# MCU.net
KiCad netlist of a schematic drawn in Altium Designer
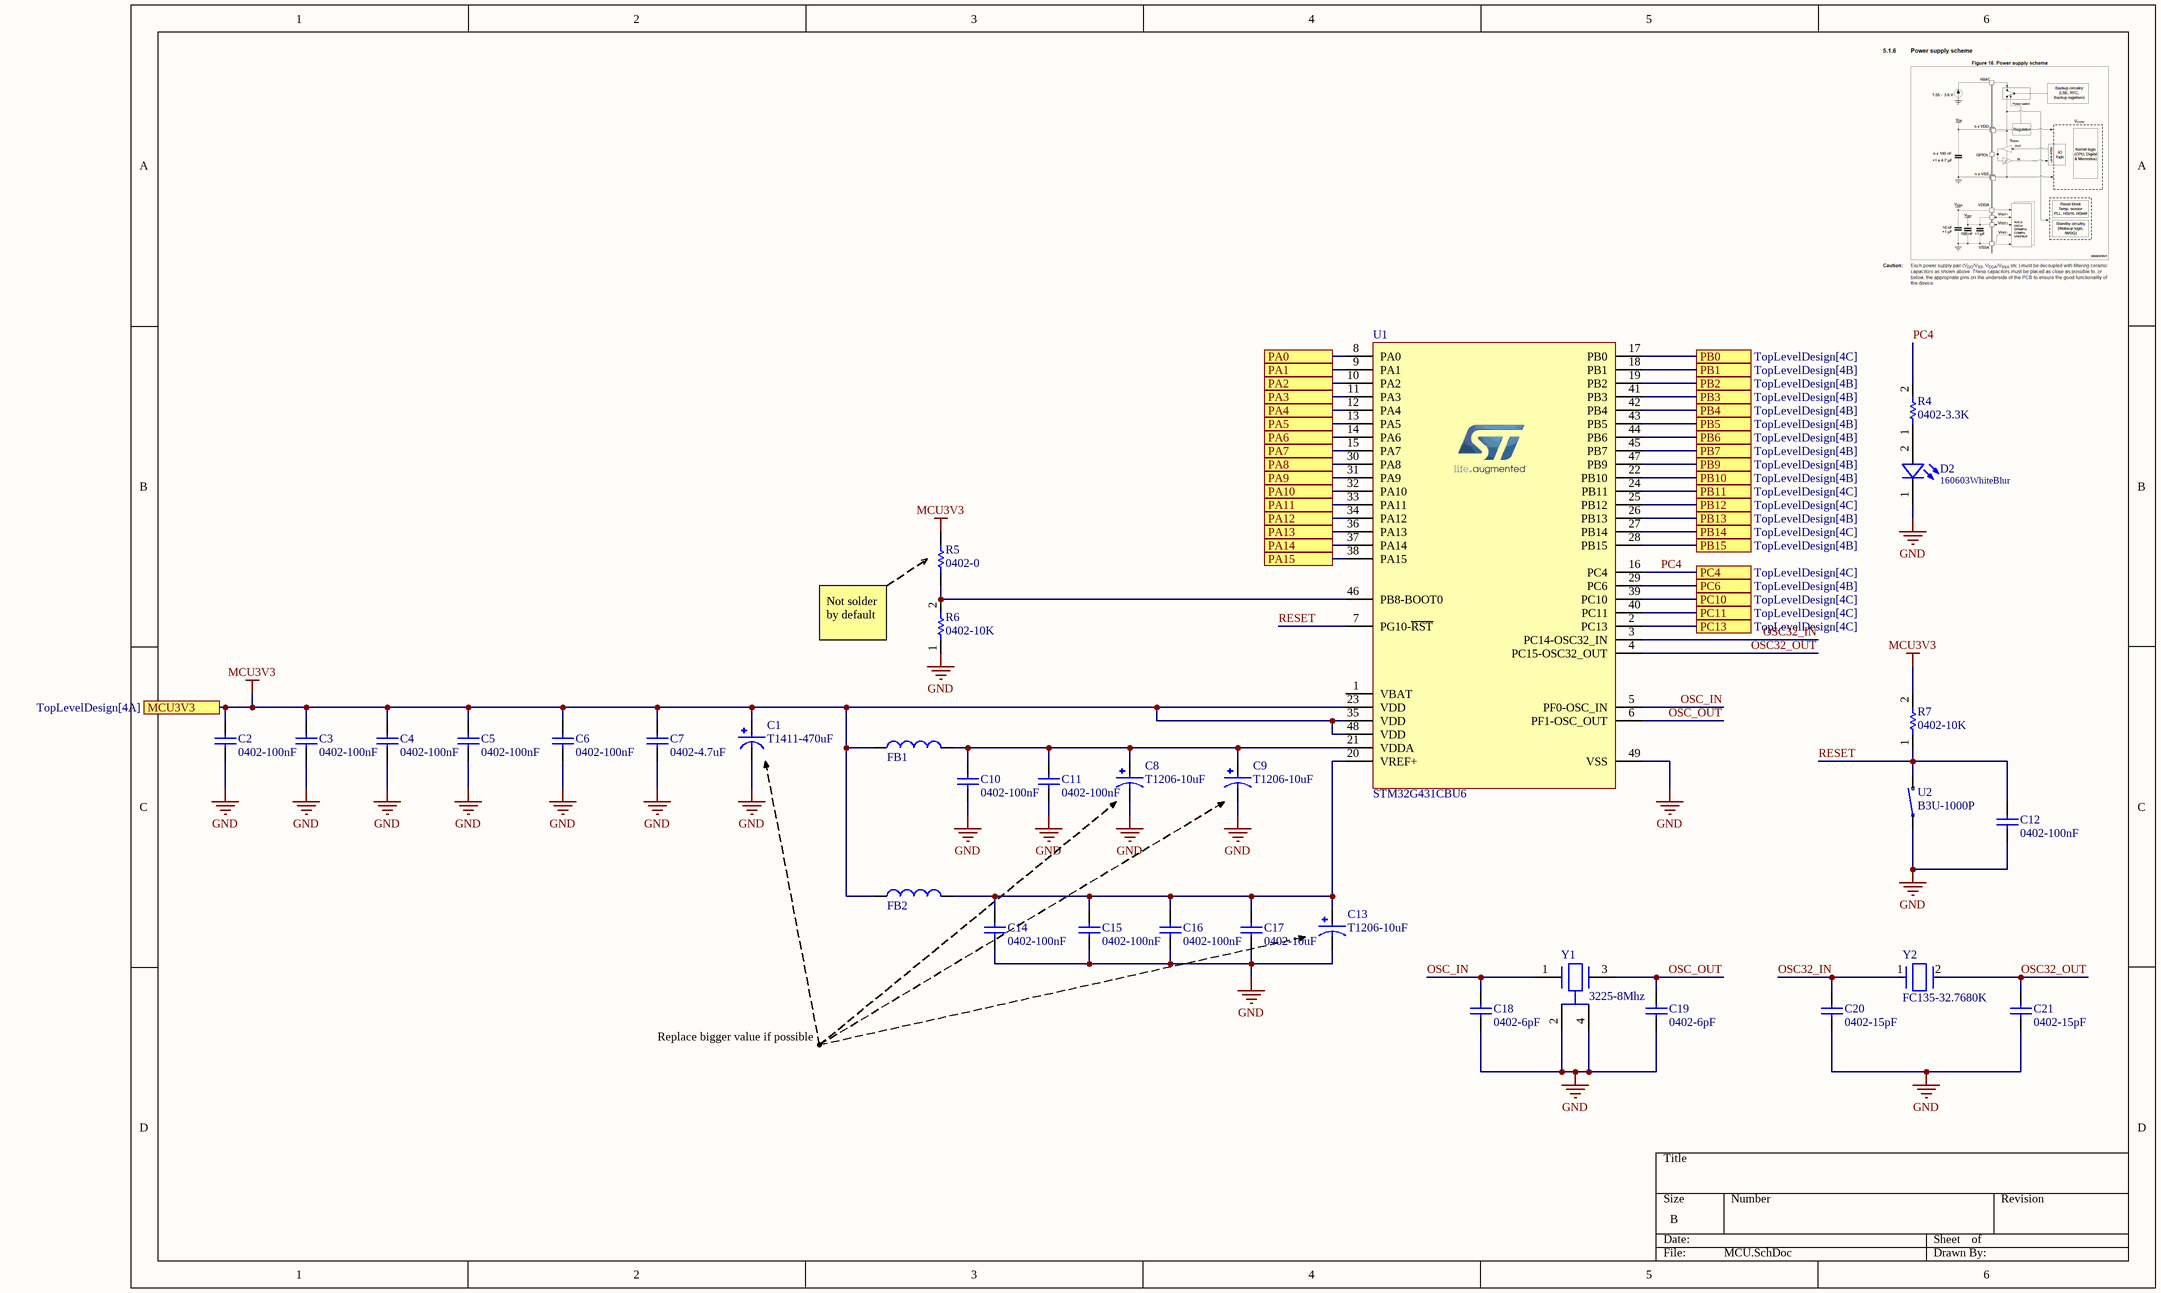
[diagram p0: MCU.SchDoc]

(export (version "E")
  (design (tool "Eeschema 10.0.6"))
  (components
    (comp (ref "C1")
      (value "T1411-470uF")
      (footprint "CAPPC3528X210N")
      (description "470 µF Molded Tantalum Polymer Capacitor 25 V 1411 (3528 Metric), 1210 150mOhm @ 100kHz")
      (fields (field (name "MP") "TCJB106M025R0150") (field (name "MF") "AVX"))
      (libsource (lib "Tin Tran") (part "T1411-10uF"))
    )
    (comp (ref "C2")
      (value "0402-100nF")
      (footprint "CAPC0402(1005)60_N")
      (description "Capacitor 100nF 0402")
      (fields (field (name "TOLERANCE") "20%"))
      (libsource (lib "Tin Tran") (part "0402"))
    )
    (comp (ref "C3")
      (value "0402-100nF")
      (footprint "CAPC0402(1005)60_N")
      (description "Capacitor 100nF 0402")
      (fields (field (name "TOLERANCE") "20%"))
      (libsource (lib "Tin Tran") (part "0402"))
    )
    (comp (ref "C4")
      (value "0402-100nF")
      (footprint "CAPC0402(1005)60_N")
      (description "Capacitor 100nF 0402")
      (fields (field (name "TOLERANCE") "20%"))
      (libsource (lib "Tin Tran") (part "0402"))
    )
    (comp (ref "C5")
      (value "0402-100nF")
      (footprint "CAPC0402(1005)60_N")
      (description "Capacitor 100nF 0402")
      (fields (field (name "TOLERANCE") "20%"))
      (libsource (lib "Tin Tran") (part "0402"))
    )
    (comp (ref "C6")
      (value "0402-100nF")
      (footprint "CAPC0402(1005)60_N")
      (description "Capacitor 100nF 0402")
      (fields (field (name "TOLERANCE") "20%"))
      (libsource (lib "Tin Tran") (part "0402"))
    )
    (comp (ref "C7")
      (value "0402-4.7uF")
      (footprint "CAPC0402(1005)60_N")
      (description "Capacitor 4.7uF 0402")
      (fields (field (name "TOLERANCE") "20%"))
      (libsource (lib "Tin Tran") (part "0402"))
    )
    (comp (ref "C8")
      (value "T1206-10uF")
      (footprint "CAPMP3216X180N")
      (description "Tantalum Capacitors - Polymer SMD 6.3V 47uF 1206 10% ESR=150mOhms")
      (fields (field (name "MP") "T543A476K006ATW150") (field (name "MF") "KEMET"))
      (libsource (lib "Tin Tran") (part "T1206-10uF"))
    )
    (comp (ref "C9")
      (value "T1206-10uF")
      (footprint "CAPMP3216X180N")
      (description "Tantalum Capacitors - Polymer SMD 6.3V 47uF 1206 10% ESR=150mOhms")
      (fields (field (name "MP") "T543A476K006ATW150") (field (name "MF") "KEMET"))
      (libsource (lib "Tin Tran") (part "T1206-10uF"))
    )
    (comp (ref "C10")
      (value "0402-100nF")
      (footprint "CAPC0402(1005)60_N")
      (description "Capacitor 100nF 0402")
      (fields (field (name "TOLERANCE") "20%"))
      (libsource (lib "Tin Tran") (part "0402"))
    )
    (comp (ref "C11")
      (value "0402-100nF")
      (footprint "CAPC0402(1005)60_N")
      (description "Capacitor 100nF 0402")
      (fields (field (name "TOLERANCE") "20%"))
      (libsource (lib "Tin Tran") (part "0402"))
    )
    (comp (ref "C12")
      (value "0402-100nF")
      (footprint "CAPC0402(1005)60_N")
      (description "Capacitor 100nF 0402")
      (fields (field (name "TOLERANCE") "20%"))
      (libsource (lib "Tin Tran") (part "0402"))
    )
    (comp (ref "C13")
      (value "T1206-10uF")
      (footprint "CAPMP3216X180N")
      (description "Tantalum Capacitors - Polymer SMD 6.3V 47uF 1206 10% ESR=150mOhms")
      (fields (field (name "MP") "T543A476K006ATW150") (field (name "MF") "KEMET"))
      (libsource (lib "Tin Tran") (part "T1206-10uF"))
    )
    (comp (ref "C14")
      (value "0402-100nF")
      (footprint "CAPC0402(1005)60_N")
      (description "Capacitor 100nF 0402")
      (fields (field (name "TOLERANCE") "20%"))
      (libsource (lib "Tin Tran") (part "0402"))
    )
    (comp (ref "C15")
      (value "0402-100nF")
      (footprint "CAPC0402(1005)60_N")
      (description "Capacitor 100nF 0402")
      (fields (field (name "TOLERANCE") "20%"))
      (libsource (lib "Tin Tran") (part "0402"))
    )
    (comp (ref "C16")
      (value "0402-100nF")
      (footprint "CAPC0402(1005)60_N")
      (description "Capacitor 100nF 0402")
      (fields (field (name "TOLERANCE") "20%"))
      (libsource (lib "Tin Tran") (part "0402"))
    )
    (comp (ref "C17")
      (value "0402-10uF")
      (footprint "CAPC0402(1005)60_N")
      (description "Capacitor 10uF 0402s")
      (fields (field (name "TOLERANCE") "20%"))
      (libsource (lib "Tin Tran") (part "0402"))
    )
    (comp (ref "C18")
      (value "0402-6pF")
      (footprint "CAPC0402(1005)60_N")
      (description "Capacitor 6pF 0402")
      (fields (field (name "TOLERANCE") "20%"))
      (libsource (lib "Tin Tran") (part "0402"))
    )
    (comp (ref "C19")
      (value "0402-6pF")
      (footprint "CAPC0402(1005)60_N")
      (description "Capacitor 6pF 0402")
      (fields (field (name "TOLERANCE") "20%"))
      (libsource (lib "Tin Tran") (part "0402"))
    )
    (comp (ref "C20")
      (value "0402-15pF")
      (footprint "CAPC0402(1005)60_N")
      (description "Capacitor 15pF 0402")
      (fields (field (name "TOLERANCE") "20%"))
      (libsource (lib "Tin Tran") (part "Copy of 0402"))
    )
    (comp (ref "C21")
      (value "0402-15pF")
      (footprint "CAPC0402(1005)60_N")
      (description "Capacitor 15pF 0402")
      (fields (field (name "TOLERANCE") "20%"))
      (libsource (lib "Tin Tran") (part "Copy of 0402"))
    )
    (comp (ref "D2")
      (value "160603WhiteBlur")
      (footprint "WL-SMCW_0603_H=0.7mm")
      (description "WL-SMCW SMT Mono-color Chip LED Blur, size 0603, White")
      (libsource (lib "Tin Tran") (part "160603WhiteClear"))
    )
    (comp (ref "FB1")
      (value "03060360110225")
      (footprint "FER_0603")
      (description "Ferrite, 0603, 600 Ohms, 300 mA")
      (fields (field (name "TOLERANCE") "25%"))
      (libsource (lib "Tin Tran") (part "03060380020125"))
    )
    (comp (ref "FB2")
      (value "03060360110225")
      (footprint "FER_0603")
      (description "Ferrite, 0603, 600 Ohms, 300 mA")
      (fields (field (name "TOLERANCE") "25%"))
      (libsource (lib "Tin Tran") (part "03060380020125"))
    )
    (comp (ref "R4")
      (value "0402-3.3K")
      (footprint "R-0402-10K")
      (description "RES 0402 3.3K")
      (libsource (lib "") (part "0402_1"))
    )
    (comp (ref "R5")
      (value "0402-0")
      (footprint "R-0402-1K")
      (description "0402Resistor 0 Ohm")
      (libsource (lib "") (part "0402_2"))
    )
    (comp (ref "R6")
      (value "0402-10K")
      (footprint "R-0402-10K")
      (description "RES 0402 10K")
      (libsource (lib "") (part "0402_1"))
    )
    (comp (ref "R7")
      (value "0402-10K")
      (footprint "R-0402-10K")
      (description "RES 0402 10K")
      (libsource (lib "") (part "0402_1"))
    )
    (comp (ref "U1")
      (value "STM32G431CBU6")
      (footprint "QFN50P700X700X60-49N")
      (fields (field (name "MF") "STMicroelectronics"))
      (libsource (lib "Tin Tran") (part "STM32G431CBU6"))
    )
    (comp (ref "U2")
      (value "B3U-1000P")
      (footprint "SODFL4025X160N")
      (description "Switch Tactile N.O. SPST Round Button Gull Wing 0.05A 12VDC 1.5N SMD T/R")
      (fields (field (name "MP") "B3U1000P") (field (name "MF") "Omron"))
      (libsource (lib "Tin Tran") (part "B3U-1000P"))
    )
    (comp (ref "Y1")
      (value "3225-8Mhz")
      (footprint "FP-NX3225SA-MFG")
      (description "CRYSTAL 8MHZ 8PF SMD")
      (fields (field (name "TOLERANCE") "15ppm") (field (name "MANUFACTURER") "NDK"))
      (libsource (lib "Tin Tran") (part "CMP-200220-000002-1"))
    )
    (comp (ref "Y2")
      (value "FC135-32.7680K")
      (footprint "FP-FC-135-MFG")
      (description "Parallel - Fundamental Quartz Crystal, 0.032768MHz Nom")
      (libsource (lib "Tin Tran") (part "c23a69dc6c9e2f18f2079038eb95dd1"))
    )
  )
  (nets
    (net (code "1") (name "/OSC32_IN") (class "Default")
      (node (ref "C20") (pin "2") (pinfunction "2_2") (pintype "passive"))
      (node (ref "U1") (pin "3") (pinfunction "PC14-OSC32_IN_3") (pintype "passive"))
      (node (ref "Y2") (pin "1") (pinfunction "1_1") (pintype "passive"))
    )
    (net (code "2") (name "/OSC32_OUT") (class "Default")
      (node (ref "C21") (pin "2") (pinfunction "2_2") (pintype "passive"))
      (node (ref "U1") (pin "4") (pinfunction "PC15-OSC32_OUT_4") (pintype "passive"))
      (node (ref "Y2") (pin "2") (pinfunction "2_2") (pintype "passive"))
    )
    (net (code "3") (name "/OSC_IN") (class "Default")
      (node (ref "C18") (pin "2") (pinfunction "2_2") (pintype "passive"))
      (node (ref "U1") (pin "5") (pinfunction "PF0-OSC_IN_5") (pintype "passive"))
      (node (ref "Y1") (pin "1") (pinfunction "1_1") (pintype "passive"))
    )
    (net (code "4") (name "/OSC_OUT") (class "Default")
      (node (ref "C19") (pin "2") (pinfunction "2_2") (pintype "passive"))
      (node (ref "U1") (pin "6") (pinfunction "PF1-OSC_OUT_6") (pintype "passive"))
      (node (ref "Y1") (pin "3") (pinfunction "3_3") (pintype "passive"))
    )
    (net (code "5") (name "/PA0") (class "Default")
      (node (ref "U1") (pin "8") (pinfunction "PA0_8") (pintype "passive"))
    )
    (net (code "6") (name "/PA1") (class "Default")
      (node (ref "U1") (pin "9") (pinfunction "PA1_9") (pintype "passive"))
    )
    (net (code "7") (name "/PA2") (class "Default")
      (node (ref "U1") (pin "10") (pinfunction "PA2_10") (pintype "passive"))
    )
    (net (code "8") (name "/PA3") (class "Default")
      (node (ref "U1") (pin "11") (pinfunction "PA3_11") (pintype "passive"))
    )
    (net (code "9") (name "/PA4") (class "Default")
      (node (ref "U1") (pin "12") (pinfunction "PA4_12") (pintype "passive"))
    )
    (net (code "10") (name "/PA5") (class "Default")
      (node (ref "U1") (pin "13") (pinfunction "PA5_13") (pintype "passive"))
    )
    (net (code "11") (name "/PA6") (class "Default")
      (node (ref "U1") (pin "14") (pinfunction "PA6_14") (pintype "passive"))
    )
    (net (code "12") (name "/PA7") (class "Default")
      (node (ref "U1") (pin "15") (pinfunction "PA7_15") (pintype "passive"))
    )
    (net (code "13") (name "/PA8") (class "Default")
      (node (ref "U1") (pin "30") (pinfunction "PA8_30") (pintype "passive"))
    )
    (net (code "14") (name "/PA9") (class "Default")
      (node (ref "U1") (pin "31") (pinfunction "PA9_31") (pintype "passive"))
    )
    (net (code "15") (name "/PA10") (class "Default")
      (node (ref "U1") (pin "32") (pinfunction "PA10_32") (pintype "passive"))
    )
    (net (code "16") (name "/PA11") (class "Default")
      (node (ref "U1") (pin "33") (pinfunction "PA11_33") (pintype "passive"))
    )
    (net (code "17") (name "/PA12") (class "Default")
      (node (ref "U1") (pin "34") (pinfunction "PA12_34") (pintype "passive"))
    )
    (net (code "18") (name "/PA13") (class "Default")
      (node (ref "U1") (pin "36") (pinfunction "PA13_36") (pintype "passive"))
    )
    (net (code "19") (name "/PA14") (class "Default")
      (node (ref "U1") (pin "37") (pinfunction "PA14_37") (pintype "passive"))
    )
    (net (code "20") (name "/PA15") (class "Default")
      (node (ref "U1") (pin "38") (pinfunction "PA15_38") (pintype "passive"))
    )
    (net (code "21") (name "/PB0") (class "Default")
      (node (ref "U1") (pin "17") (pinfunction "PB0_17") (pintype "passive"))
    )
    (net (code "22") (name "/PB1") (class "Default")
      (node (ref "U1") (pin "18") (pinfunction "PB1_18") (pintype "passive"))
    )
    (net (code "23") (name "/PB2") (class "Default")
      (node (ref "U1") (pin "19") (pinfunction "PB2_19") (pintype "passive"))
    )
    (net (code "24") (name "/PB3") (class "Default")
      (node (ref "U1") (pin "41") (pinfunction "PB3_41") (pintype "passive"))
    )
    (net (code "25") (name "/PB4") (class "Default")
      (node (ref "U1") (pin "42") (pinfunction "PB4_42") (pintype "passive"))
    )
    (net (code "26") (name "/PB5") (class "Default")
      (node (ref "U1") (pin "43") (pinfunction "PB5_43") (pintype "passive"))
    )
    (net (code "27") (name "/PB6") (class "Default")
      (node (ref "U1") (pin "44") (pinfunction "PB6_44") (pintype "passive"))
    )
    (net (code "28") (name "/PB7") (class "Default")
      (node (ref "U1") (pin "45") (pinfunction "PB7_45") (pintype "passive"))
    )
    (net (code "29") (name "/PB9") (class "Default")
      (node (ref "U1") (pin "47") (pinfunction "PB9_47") (pintype "passive"))
    )
    (net (code "30") (name "/PB10") (class "Default")
      (node (ref "U1") (pin "22") (pinfunction "PB10_22") (pintype "passive"))
    )
    (net (code "31") (name "/PB11") (class "Default")
      (node (ref "U1") (pin "24") (pinfunction "PB11_24") (pintype "passive"))
    )
    (net (code "32") (name "/PB12") (class "Default")
      (node (ref "U1") (pin "25") (pinfunction "PB12_25") (pintype "passive"))
    )
    (net (code "33") (name "/PB13") (class "Default")
      (node (ref "U1") (pin "26") (pinfunction "PB13_26") (pintype "passive"))
    )
    (net (code "34") (name "/PB14") (class "Default")
      (node (ref "U1") (pin "27") (pinfunction "PB14_27") (pintype "passive"))
    )
    (net (code "35") (name "/PB15") (class "Default")
      (node (ref "U1") (pin "28") (pinfunction "PB15_28") (pintype "passive"))
    )
    (net (code "36") (name "/PC4") (class "Default")
      (node (ref "R4") (pin "2") (pinfunction "2_2") (pintype "passive"))
      (node (ref "U1") (pin "16") (pinfunction "PC4_16") (pintype "passive"))
    )
    (net (code "37") (name "/PC6") (class "Default")
      (node (ref "U1") (pin "29") (pinfunction "PC6_29") (pintype "passive"))
    )
    (net (code "38") (name "/PC10") (class "Default")
      (node (ref "U1") (pin "39") (pinfunction "PC10_39") (pintype "passive"))
    )
    (net (code "39") (name "/PC11") (class "Default")
      (node (ref "U1") (pin "40") (pinfunction "PC11_40") (pintype "passive"))
    )
    (net (code "40") (name "/PC13") (class "Default")
      (node (ref "U1") (pin "2") (pinfunction "PC13_2") (pintype "passive"))
    )
    (net (code "41") (name "/RESET") (class "Default")
      (node (ref "C12") (pin "2") (pinfunction "2_2") (pintype "passive"))
      (node (ref "R7") (pin "1") (pinfunction "1_1") (pintype "passive"))
      (node (ref "U1") (pin "7") (pinfunction "PG10-~{RST}_7") (pintype "passive"))
      (node (ref "U2") (pin "2") (pinfunction "2_2") (pintype "passive"))
    )
    (net (code "42") (name "GND") (class "Default")
      (node (ref "C1") (pin "2") (pinfunction "2_2") (pintype "passive"))
      (node (ref "C10") (pin "1") (pinfunction "1_1") (pintype "passive"))
      (node (ref "C11") (pin "1") (pinfunction "1_1") (pintype "passive"))
      (node (ref "C12") (pin "1") (pinfunction "1_1") (pintype "passive"))
      (node (ref "C13") (pin "2") (pinfunction "2_2") (pintype "passive"))
      (node (ref "C14") (pin "1") (pinfunction "1_1") (pintype "passive"))
      (node (ref "C15") (pin "1") (pinfunction "1_1") (pintype "passive"))
      (node (ref "C16") (pin "1") (pinfunction "1_1") (pintype "passive"))
      (node (ref "C17") (pin "1") (pinfunction "1_1") (pintype "passive"))
      (node (ref "C18") (pin "1") (pinfunction "1_1") (pintype "passive"))
      (node (ref "C19") (pin "1") (pinfunction "1_1") (pintype "passive"))
      (node (ref "C2") (pin "1") (pinfunction "1_1") (pintype "passive"))
      (node (ref "C20") (pin "1") (pinfunction "1_1") (pintype "passive"))
      (node (ref "C21") (pin "1") (pinfunction "1_1") (pintype "passive"))
      (node (ref "C3") (pin "1") (pinfunction "1_1") (pintype "passive"))
      (node (ref "C4") (pin "1") (pinfunction "1_1") (pintype "passive"))
      (node (ref "C5") (pin "1") (pinfunction "1_1") (pintype "passive"))
      (node (ref "C6") (pin "1") (pinfunction "1_1") (pintype "passive"))
      (node (ref "C7") (pin "1") (pinfunction "1_1") (pintype "passive"))
      (node (ref "C8") (pin "2") (pinfunction "2_2") (pintype "passive"))
      (node (ref "C9") (pin "2") (pinfunction "2_2") (pintype "passive"))
      (node (ref "D2") (pin "1") (pinfunction "K_1") (pintype "passive"))
      (node (ref "R6") (pin "1") (pinfunction "1_1") (pintype "passive"))
      (node (ref "U1") (pin "49") (pinfunction "VSS_49") (pintype "passive"))
      (node (ref "U2") (pin "1") (pinfunction "1_1") (pintype "passive"))
      (node (ref "Y1") (pin "2") (pinfunction "GND_2") (pintype "power_in"))
      (node (ref "Y1") (pin "4") (pinfunction "GND_4") (pintype "power_in"))
    )
    (net (code "43") (name "MCU3V3") (class "Default")
      (node (ref "C1") (pin "1") (pinfunction "1_1") (pintype "passive"))
      (node (ref "C2") (pin "2") (pinfunction "2_2") (pintype "passive"))
      (node (ref "C3") (pin "2") (pinfunction "2_2") (pintype "passive"))
      (node (ref "C4") (pin "2") (pinfunction "2_2") (pintype "passive"))
      (node (ref "C5") (pin "2") (pinfunction "2_2") (pintype "passive"))
      (node (ref "C6") (pin "2") (pinfunction "2_2") (pintype "passive"))
      (node (ref "C7") (pin "2") (pinfunction "2_2") (pintype "passive"))
      (node (ref "FB1") (pin "1") (pinfunction "1_1") (pintype "passive"))
      (node (ref "FB2") (pin "1") (pinfunction "1_1") (pintype "passive"))
      (node (ref "R5") (pin "2") (pinfunction "2_2") (pintype "passive"))
      (node (ref "R7") (pin "2") (pinfunction "2_2") (pintype "passive"))
      (node (ref "U1") (pin "23") (pinfunction "VDD_23") (pintype "passive"))
      (node (ref "U1") (pin "35") (pinfunction "VDD_35") (pintype "passive"))
      (node (ref "U1") (pin "48") (pinfunction "VDD_48") (pintype "passive"))
    )
    (net (code "44") (name "Net-(D2-A)") (class "Default")
      (node (ref "D2") (pin "2") (pinfunction "A_2") (pintype "passive"))
      (node (ref "R4") (pin "1") (pinfunction "1_1") (pintype "passive"))
    )
    (net (code "45") (name "Net-(U1-PB8-BOOT0)") (class "Default")
      (node (ref "R5") (pin "1") (pinfunction "1_1") (pintype "passive"))
      (node (ref "R6") (pin "2") (pinfunction "2_2") (pintype "passive"))
      (node (ref "U1") (pin "46") (pinfunction "PB8-BOOT0_46") (pintype "passive"))
    )
    (net (code "46") (name "Net-(U1-VDDA)") (class "Default")
      (node (ref "C10") (pin "2") (pinfunction "2_2") (pintype "passive"))
      (node (ref "C11") (pin "2") (pinfunction "2_2") (pintype "passive"))
      (node (ref "C8") (pin "1") (pinfunction "1_1") (pintype "passive"))
      (node (ref "C9") (pin "1") (pinfunction "1_1") (pintype "passive"))
      (node (ref "FB1") (pin "2") (pinfunction "2_2") (pintype "passive"))
      (node (ref "U1") (pin "21") (pinfunction "VDDA_21") (pintype "passive"))
    )
    (net (code "47") (name "Net-(U1-VREF+)") (class "Default")
      (node (ref "C13") (pin "1") (pinfunction "1_1") (pintype "passive"))
      (node (ref "C14") (pin "2") (pinfunction "2_2") (pintype "passive"))
      (node (ref "C15") (pin "2") (pinfunction "2_2") (pintype "passive"))
      (node (ref "C16") (pin "2") (pinfunction "2_2") (pintype "passive"))
      (node (ref "C17") (pin "2") (pinfunction "2_2") (pintype "passive"))
      (node (ref "FB2") (pin "2") (pinfunction "2_2") (pintype "passive"))
      (node (ref "U1") (pin "20") (pinfunction "VREF+_20") (pintype "passive"))
    )
    (net (code "48") (name "unconnected-(U1-VBAT-Pad1)") (class "Default")
      (node (ref "U1") (pin "1") (pinfunction "VBAT_1") (pintype "passive"))
    )
  )
)
